# AirU_v2_0.net
KiCad netlist of a schematic drawn in EAGLE
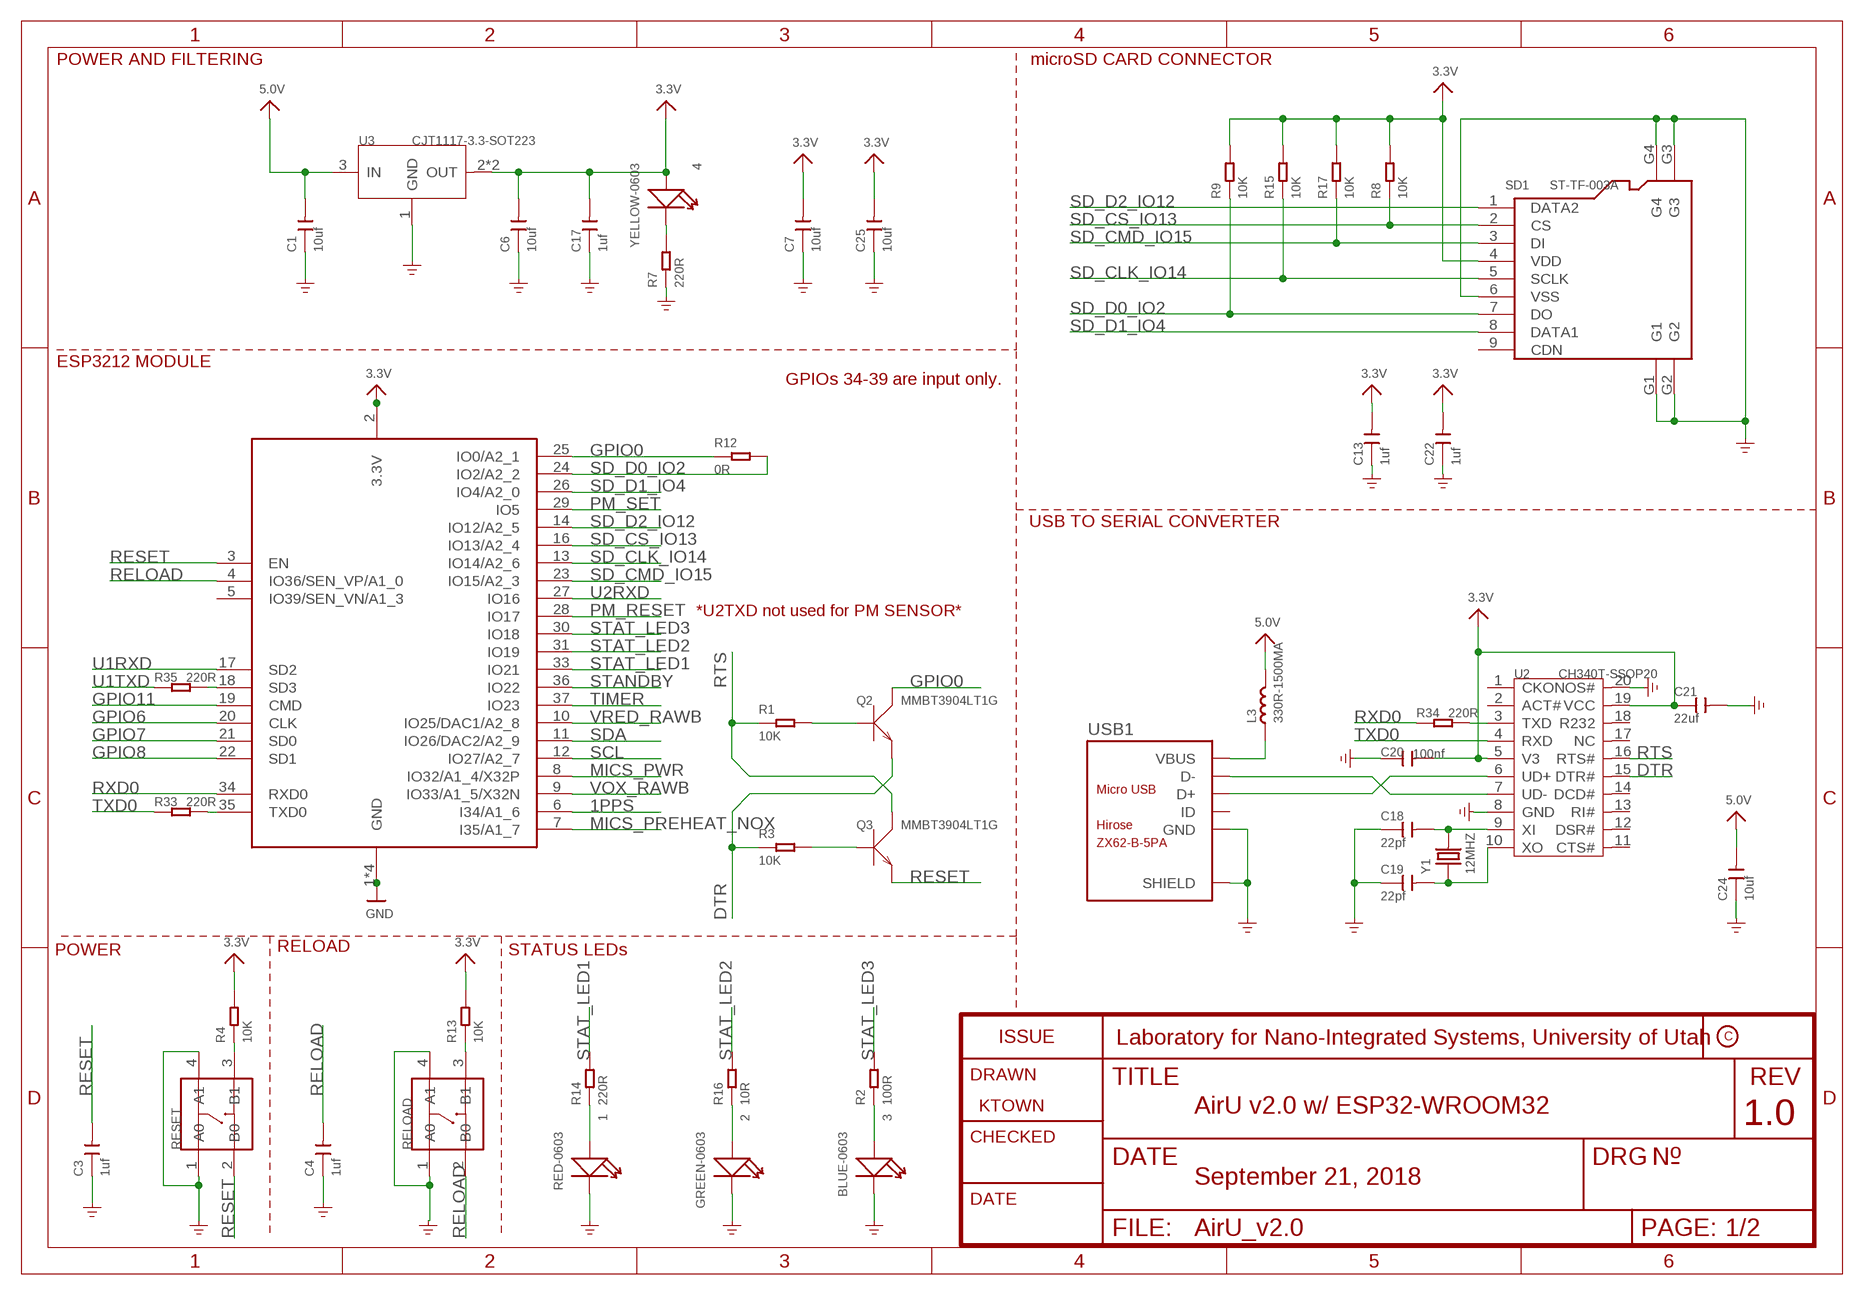
[diagram p0: schematic, sheet 1]
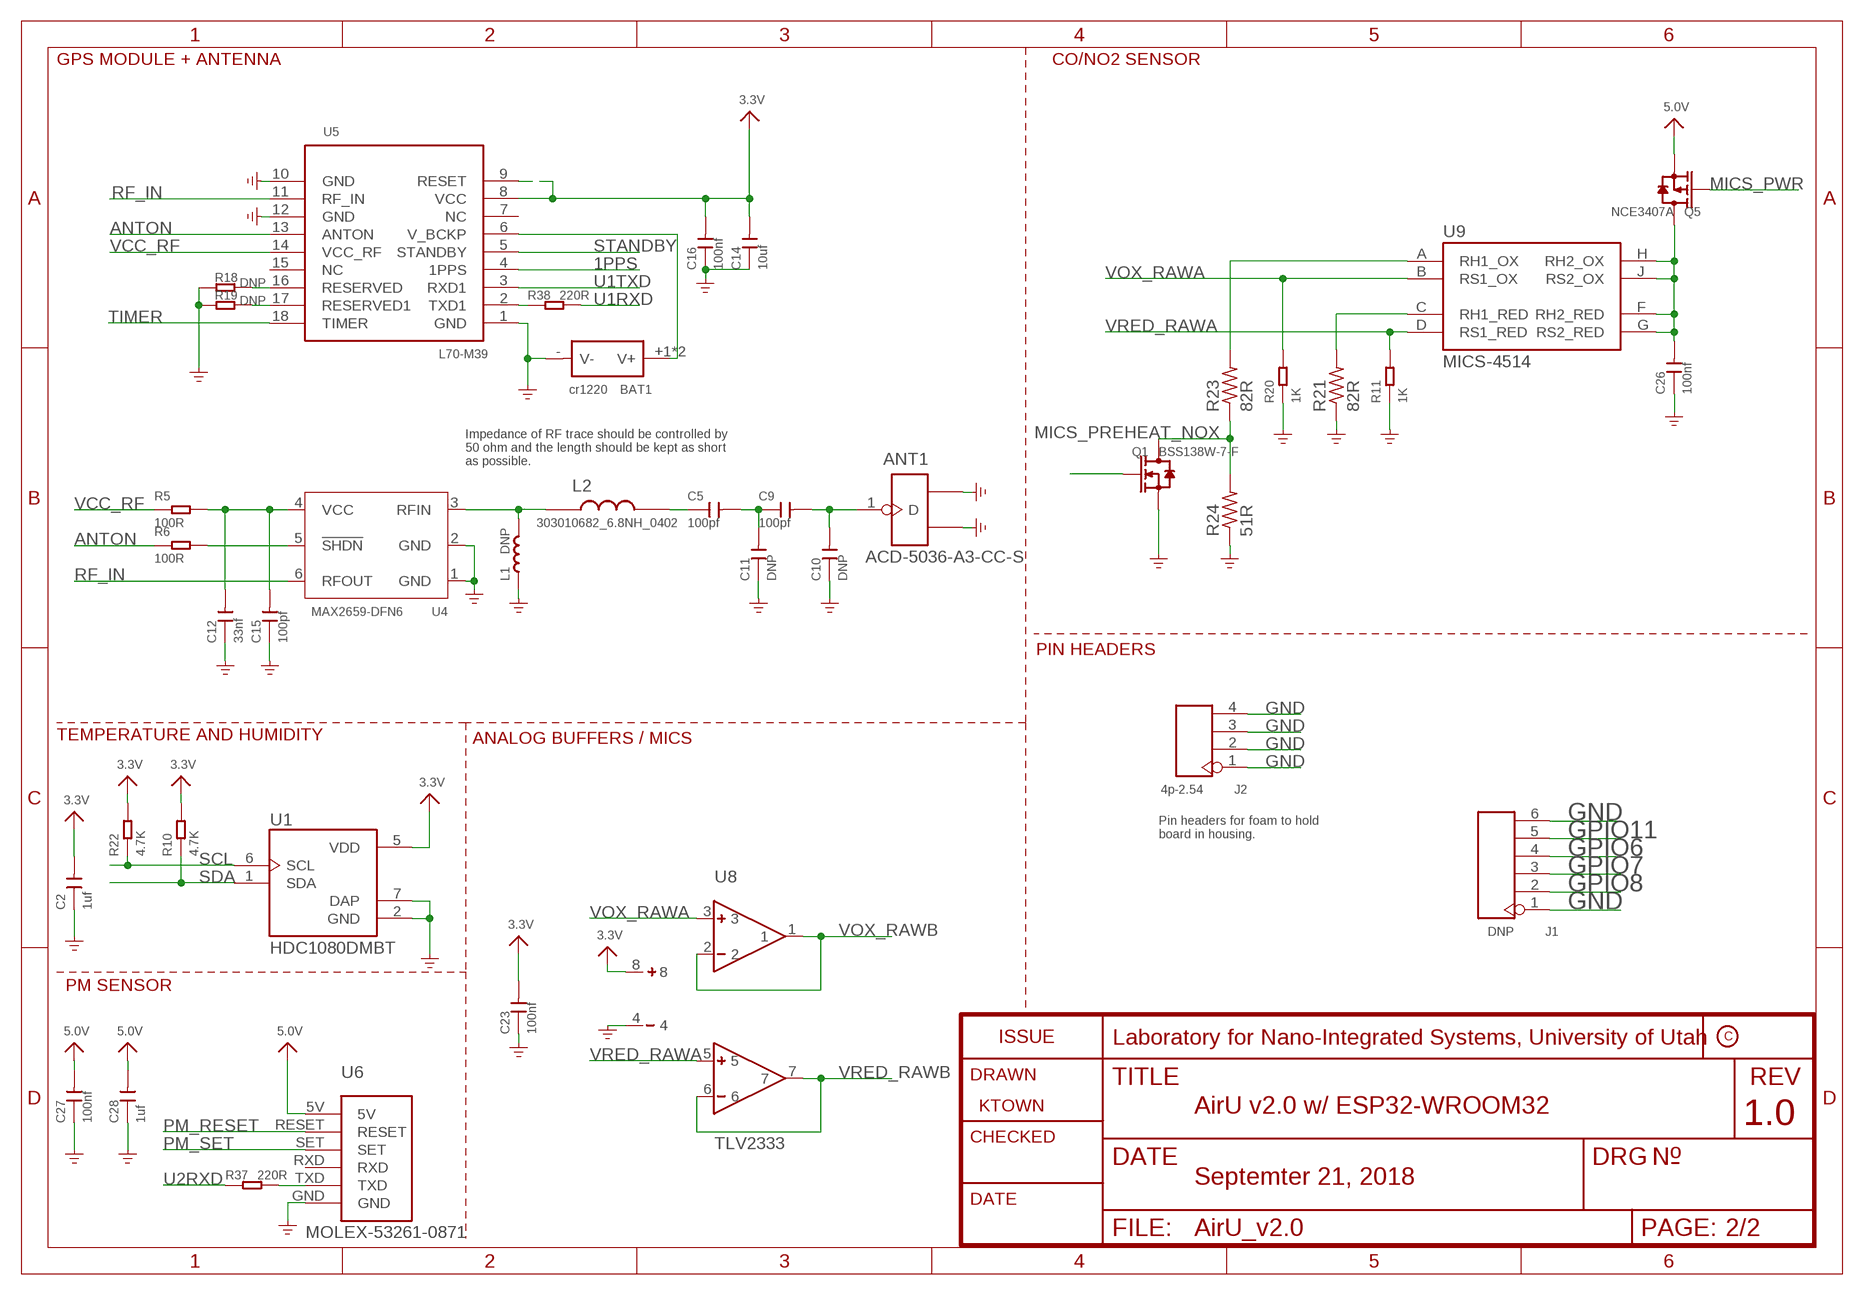
[diagram p1: schematic, sheet 2]

(export (version "E")
  (design (tool "Eeschema 10.0.6"))
  (components
    (comp (ref "1")
      (value "RED-0603")
      (footprint "eagle-import:LED-0603")
      (fields (field (name "MPN") "19-217-R6C-AL1M2VY-3T"))
      (libsource (lib "eagle-import") (part "LED-SMD-RED-DIFFUSED(0603)"))
    )
    (comp (ref "2")
      (value "GREEN-0603")
      (footprint "eagle-import:LED-0603")
      (fields (field (name "MPN") "19-217-G7C-AN1P2-3T"))
      (libsource (lib "eagle-import") (part "SMD-LED-CLEAR-GREEN(0603)"))
    )
    (comp (ref "3")
      (value "BLUE-0603")
      (footprint "eagle-import:LED-0603")
      (fields (field (name "MPN") "19-217-BHC-ZL1M2RY-3T"))
      (libsource (lib "eagle-import") (part "SMD-LED-CLEAR-BLUE(0603)"))
    )
    (comp (ref "4")
      (value "YELLOW-0603")
      (footprint "eagle-import:LED-0603")
      (fields (field (name "MPN") "19-217-Y5C-AM1N1VY-3T"))
      (libsource (lib "eagle-import") (part "SMD-LED-CLEAR-YELLOW(0603)"))
    )
    (comp (ref "C1")
      (value "10uf")
      (footprint "eagle-import:C0603")
      (fields (field (name "MPN") "CC0603KRX5R6BB106"))
      (libsource (lib "eagle-import") (part "CERAMIC-10UF-10V-10%-X5R(0603)"))
    )
    (comp (ref "C3")
      (value "1uf")
      (footprint "eagle-import:C0603")
      (fields (field (name "MPN") "CC0603KRX7R8BB105"))
      (libsource (lib "eagle-import") (part "CERAMIC-1UF-25V-10%-X7R(0603)"))
    )
    (comp (ref "C4")
      (value "1uf")
      (footprint "eagle-import:C0603")
      (fields (field (name "MPN") "CC0603KRX7R8BB105"))
      (libsource (lib "eagle-import") (part "CERAMIC-1UF-25V-10%-X7R(0603)"))
    )
    (comp (ref "C6")
      (value "10uf")
      (footprint "eagle-import:C0603")
      (fields (field (name "MPN") "CC0603KRX5R6BB106"))
      (libsource (lib "eagle-import") (part "CERAMIC-10UF-10V-10%-X5R(0603)"))
    )
    (comp (ref "C7")
      (value "10uf")
      (footprint "eagle-import:C0603")
      (fields (field (name "MPN") "CC0603KRX5R6BB106"))
      (libsource (lib "eagle-import") (part "CERAMIC-10UF-10V-10%-X5R(0603)"))
    )
    (comp (ref "C13")
      (value "1uf")
      (footprint "eagle-import:C0603")
      (fields (field (name "MPN") "CC0603KRX7R8BB105"))
      (libsource (lib "eagle-import") (part "CERAMIC-1UF-25V-10%-X7R(0603)"))
    )
    (comp (ref "C17")
      (value "1uf")
      (footprint "eagle-import:C0603")
      (fields (field (name "MPN") "CC0603KRX7R8BB105"))
      (libsource (lib "eagle-import") (part "CERAMIC-1UF-25V-10%-X7R(0603)"))
    )
    (comp (ref "C18")
      (value "22pf")
      (footprint "eagle-import:C0603")
      (fields (field (name "MPN") "CC0603JRNPO9BN220"))
      (libsource (lib "eagle-import") (part "CERAMIC-22PF-50V-5%-NPO(0603)"))
    )
    (comp (ref "C19")
      (value "22pf")
      (footprint "eagle-import:C0603")
      (fields (field (name "MPN") "CC0603JRNPO9BN220"))
      (libsource (lib "eagle-import") (part "CERAMIC-22PF-50V-5%-NPO(0603)"))
    )
    (comp (ref "C20")
      (value "100nf")
      (footprint "eagle-import:C0603")
      (fields (field (name "MPN") "CC0603KRX7R9BB104"))
      (libsource (lib "eagle-import") (part "CERAMIC-100NF-50V-10%-X7R(0603)"))
    )
    (comp (ref "C21")
      (value "22uf")
      (footprint "eagle-import:C0805")
      (fields (field (name "MPN") "CC0805MKX5R5BB226"))
      (libsource (lib "eagle-import") (part "CERAMIC-22UF-6.3V-20%-X5R(0805)"))
    )
    (comp (ref "C22")
      (value "1uf")
      (footprint "eagle-import:C0603")
      (fields (field (name "MPN") "CC0603KRX7R8BB105"))
      (libsource (lib "eagle-import") (part "CERAMIC-1UF-25V-10%-X7R(0603)"))
    )
    (comp (ref "C24")
      (value "10uf")
      (footprint "eagle-import:C0603")
      (fields (field (name "MPN") "CC0603KRX5R6BB106"))
      (libsource (lib "eagle-import") (part "CERAMIC-10UF-10V-10%-X5R(0603)"))
    )
    (comp (ref "C25")
      (value "10uf")
      (footprint "eagle-import:C0603")
      (fields (field (name "MPN") "CC0603KRX5R6BB106"))
      (libsource (lib "eagle-import") (part "CERAMIC-10UF-10V-10%-X5R(0603)"))
    )
    (comp (ref "L3")
      (value "330R-1500MA")
      (footprint "eagle-import:L0805")
      (fields (field (name "MPN") "BLM21PG331SN1D"))
      (libsource (lib "eagle-import") (part "SMD-FERRITE-BEAD-330R-1500MA(0805)'0805'"))
    )
    (comp (ref "Q2")
      (value "MMBT3904LT1G")
      (footprint "eagle-import:SOT-23")
      (libsource (lib "eagle-import") (part "SMD-TRANSISTORS-NPN-40V-200MA-MMBT3904LT1G(SOT-23)"))
    )
    (comp (ref "Q3")
      (value "MMBT3904LT1G")
      (footprint "eagle-import:SOT-23")
      (libsource (lib "eagle-import") (part "SMD-TRANSISTORS-NPN-40V-200MA-MMBT3904LT1G(SOT-23)"))
    )
    (comp (ref "R1")
      (value "10K")
      (footprint "eagle-import:R0603")
      (fields (field (name "MPN") "RC0603FR-0710KL"))
      (libsource (lib "eagle-import") (part "SMD-RES-10K-1%-1/10W(0603)"))
    )
    (comp (ref "R2")
      (value "100R")
      (footprint "eagle-import:R0603")
      (fields (field (name "MPN") "RC0603JR-07100RL"))
      (libsource (lib "eagle-import") (part "SMD-RES-100R-5%-1/10W(0603)"))
    )
    (comp (ref "R3")
      (value "10K")
      (footprint "eagle-import:R0603")
      (fields (field (name "MPN") "RC0603FR-0710KL"))
      (libsource (lib "eagle-import") (part "SMD-RES-10K-1%-1/10W(0603)"))
    )
    (comp (ref "R4")
      (value "10K")
      (footprint "eagle-import:R0603")
      (fields (field (name "MPN") "RC0603FR-0710KL"))
      (libsource (lib "eagle-import") (part "SMD-RES-10K-1%-1/10W(0603)"))
    )
    (comp (ref "R7")
      (value "220R")
      (footprint "eagle-import:R0603")
      (fields (field (name "MPN") "RC0603JR-07220RL"))
      (libsource (lib "eagle-import") (part "SMD-RES-220R-5%-1/10W(0603)"))
    )
    (comp (ref "R8")
      (value "10K")
      (footprint "eagle-import:R0603")
      (fields (field (name "MPN") "RC0603FR-0710KL"))
      (libsource (lib "eagle-import") (part "SMD-RES-10K-1%-1/10W(0603)"))
    )
    (comp (ref "R9")
      (value "10K")
      (footprint "eagle-import:R0603")
      (fields (field (name "MPN") "RC0603FR-0710KL"))
      (libsource (lib "eagle-import") (part "SMD-RES-10K-1%-1/10W(0603)"))
    )
    (comp (ref "R12")
      (value "0R")
      (footprint "eagle-import:R0603")
      (fields (field (name "MPN") "RC0603JR-070RL"))
      (libsource (lib "eagle-import") (part "SMD-RES-0R-5%-1/10W(0603)"))
    )
    (comp (ref "R13")
      (value "10K")
      (footprint "eagle-import:R0603")
      (fields (field (name "MPN") "RC0603FR-0710KL"))
      (libsource (lib "eagle-import") (part "SMD-RES-10K-1%-1/10W(0603)"))
    )
    (comp (ref "R14")
      (value "220R")
      (footprint "eagle-import:R0603")
      (fields (field (name "MPN") "RC0603JR-07220RL"))
      (libsource (lib "eagle-import") (part "SMD-RES-220R-5%-1/10W(0603)"))
    )
    (comp (ref "R15")
      (value "10K")
      (footprint "eagle-import:R0603")
      (fields (field (name "MPN") "RC0603FR-0710KL"))
      (libsource (lib "eagle-import") (part "SMD-RES-10K-1%-1/10W(0603)"))
    )
    (comp (ref "R16")
      (value "10R")
      (footprint "eagle-import:R0603")
      (fields (field (name "MPN") "RC0603JR-0710RL"))
      (libsource (lib "eagle-import") (part "SMD-RES-10R-5%-1/10W(0603)"))
    )
    (comp (ref "R17")
      (value "10K")
      (footprint "eagle-import:R0603")
      (fields (field (name "MPN") "RC0603FR-0710KL"))
      (libsource (lib "eagle-import") (part "SMD-RES-10K-1%-1/10W(0603)"))
    )
    (comp (ref "R33")
      (value "220R")
      (footprint "eagle-import:R0603")
      (fields (field (name "MPN") "RC0603JR-07220RL"))
      (libsource (lib "eagle-import") (part "SMD-RES-220R-5%-1/10W(0603)"))
    )
    (comp (ref "R34")
      (value "220R")
      (footprint "eagle-import:R0603")
      (fields (field (name "MPN") "RC0603JR-07220RL"))
      (libsource (lib "eagle-import") (part "SMD-RES-220R-5%-1/10W(0603)"))
    )
    (comp (ref "R35")
      (value "220R")
      (footprint "eagle-import:R0603")
      (fields (field (name "MPN") "RC0603JR-07220RL"))
      (libsource (lib "eagle-import") (part "SMD-RES-220R-5%-1/10W(0603)"))
    )
    (comp (ref "RELOAD")
      (value "DIP-SWITCH-TACTILE-SPST-NO/TS-1109(4P-D6.0MM)'TS-1109'")
      (footprint "eagle-import:SW4-6.0X6.0X5.0MM")
      (libsource (lib "eagle-import") (part "DIP-SWITCH-TACTILE-SPST-NO/TS-1109(4P-D6.0MM)'TS-1109'"))
    )
    (comp (ref "RESET")
      (value "DIP-SWITCH-TACTILE-SPST-NO/TS-1109(4P-D6.0MM)'TS-1109'")
      (footprint "eagle-import:SW4-6.0X6.0X5.0MM")
      (libsource (lib "eagle-import") (part "DIP-SWITCH-TACTILE-SPST-NO/TS-1109(4P-D6.0MM)'TS-1109'"))
    )
    (comp (ref "SD1")
      (value "ST-TF-003A")
      (footprint "eagle-import:MICRO-SD9+4P-SMD-16.1X14.5X1.85MM")
      (libsource (lib "eagle-import") (part "MICRO-SD-CARD-SOCKET-9P(ST-TF-003A)"))
    )
    (comp (ref "U2")
      (value "CH340T-SSOP20")
      (footprint "eagle-import:SSOP20-0.65-7.6X5.2MM")
      (fields (field (name "MPN") "CH340T"))
      (libsource (lib "eagle-import") (part "INTERFACE-CH340T(SSOP20)"))
    )
    (comp (ref "U3")
      (value "CJT1117-3.3-SOT223")
      (footprint "eagle-import:SOT-223")
      (fields (field (name "MPN") "CJT1117-3.3"))
      (libsource (lib "eagle-import") (part "PMIC-CJT1117-3.3(SOT223)"))
    )
    (comp (ref "U7")
      (value "ESP32_WROOM32_SKINNY")
      (footprint "eagle-import:WROOM32_SKINNY")
      (libsource (lib "eagle-import") (part "ESP32_WROOM32_SKINNY"))
    )
    (comp (ref "USB1")
      (value "ZX62-B-5PA")
      (footprint "eagle-import:MICRO-USB5+6P-SMD-0.65-AB")
      (libsource (lib "eagle-import") (part "MICRO-USB-SMD(ZX62-B-5PA)"))
    )
    (comp (ref "Y1")
      (value "12MHZ")
      (footprint "eagle-import:X2-SMD-5.0X3.2X1.3MM")
      (fields (field (name "MPN") "5032/2P"))
      (libsource (lib "eagle-import") (part "SMD-CRYSTAL-12MHZ-20PF-20PPM-40R(2P-5.0X3.2MM)"))
    )
    (comp (ref "ANT1")
      (value "ACD-5036-A3-CC-S")
      (footprint "eagle-import:ANT3-SMD-5.2X3.7X0.7MM")
      (libsource (lib "eagle-import") (part "ANTENNA-ACD5036"))
    )
    (comp (ref "BAT1")
      (value "cr1220")
      (footprint "eagle-import:BAT2P-13.5-CR1220")
      (libsource (lib "eagle-import") (part "DIP-BATTERY-CELL-HOLDER(1220)"))
    )
    (comp (ref "C2")
      (value "1uf")
      (footprint "eagle-import:C0603")
      (fields (field (name "MPN") "CC0603KRX7R8BB105"))
      (libsource (lib "eagle-import") (part "CERAMIC-1UF-25V-10%-X7R(0603)"))
    )
    (comp (ref "C5")
      (value "100pf")
      (footprint "eagle-import:C0603")
      (fields (field (name "MPN") "CC0603JRNPO9BN101"))
      (libsource (lib "eagle-import") (part "CERAMIC-100PF-50V-5%-NPO(0603)"))
    )
    (comp (ref "C9")
      (value "100pf")
      (footprint "eagle-import:C0603")
      (fields (field (name "MPN") "CC0603JRNPO9BN101"))
      (libsource (lib "eagle-import") (part "CERAMIC-100PF-50V-5%-NPO(0603)"))
    )
    (comp (ref "C10")
      (value "DNP")
      (footprint "eagle-import:C0603")
      (fields (field (name "MPN") "CC0603JRNPO9BN101"))
      (libsource (lib "eagle-import") (part "CERAMIC-100PF-50V-5%-NPO(0603)"))
    )
    (comp (ref "C11")
      (value "DNP")
      (footprint "eagle-import:C0603")
      (fields (field (name "MPN") "CC0603JRNPO9BN101"))
      (libsource (lib "eagle-import") (part "CERAMIC-100PF-50V-5%-NPO(0603)"))
    )
    (comp (ref "C12")
      (value "33nf")
      (footprint "eagle-import:C0603")
      (fields (field (name "MPN") "CC0603KRX7R9BB333"))
      (libsource (lib "eagle-import") (part "CERAMIC-33NF-50V-10%-X7R(0603)"))
    )
    (comp (ref "C14")
      (value "10uf")
      (footprint "eagle-import:C0603")
      (fields (field (name "MPN") "CC0603KRX5R6BB106"))
      (libsource (lib "eagle-import") (part "CERAMIC-10UF-10V-10%-X5R(0603)"))
    )
    (comp (ref "C15")
      (value "100pf")
      (footprint "eagle-import:C0603")
      (fields (field (name "MPN") "CC0603JRNPO9BN101"))
      (libsource (lib "eagle-import") (part "CERAMIC-100PF-50V-5%-NPO(0603)"))
    )
    (comp (ref "C16")
      (value "100nf")
      (footprint "eagle-import:C0603")
      (fields (field (name "MPN") "CC0603KRX7R9BB104"))
      (libsource (lib "eagle-import") (part "CERAMIC-100NF-50V-10%-X7R(0603)"))
    )
    (comp (ref "C23")
      (value "100nf")
      (footprint "eagle-import:C0603")
      (fields (field (name "MPN") "CC0603KRX7R9BB104"))
      (libsource (lib "eagle-import") (part "CERAMIC-100NF-50V-10%-X7R(0603)"))
    )
    (comp (ref "C26")
      (value "100nf")
      (footprint "eagle-import:C0603")
      (fields (field (name "MPN") "CC0603KRX7R9BB104"))
      (libsource (lib "eagle-import") (part "CERAMIC-100NF-50V-10%-X7R(0603)"))
    )
    (comp (ref "C27")
      (value "100nf")
      (footprint "eagle-import:C0603")
      (fields (field (name "MPN") "CC0603KRX7R9BB104"))
      (libsource (lib "eagle-import") (part "CERAMIC-100NF-50V-10%-X7R(0603)"))
    )
    (comp (ref "C28")
      (value "1uf")
      (footprint "eagle-import:C0603")
      (fields (field (name "MPN") "CC0603KRX7R8BB105"))
      (libsource (lib "eagle-import") (part "CERAMIC-1UF-25V-10%-X7R(0603)"))
    )
    (comp (ref "J1")
      (value "DNP")
      (footprint "eagle-import:H6-2.54")
      (fields (field (name "MPN") "P125-1106A1BS116A1"))
      (libsource (lib "eagle-import") (part "DIP-BLACK-MALE-HEADER(6P-2.54)"))
    )
    (comp (ref "J2")
      (value "4p-2.54")
      (footprint "eagle-import:H4-2.54")
      (fields (field (name "MPN") "P125-1104A0BS116A1"))
      (libsource (lib "eagle-import") (part "DIP-BLACK-MALE-HEADER-VERT(4P-2.54)"))
    )
    (comp (ref "L1")
      (value "DNP")
      (footprint "eagle-import:L0201")
      (libsource (lib "eagle-import") (part "INDUCTOR/FERRITE-BEAD-0201"))
    )
    (comp (ref "L2")
      (value "303010682_6.8NH_0402")
      (footprint "eagle-import:L0402")
      (libsource (lib "eagle-import") (part "303010682_6.8NH_0402"))
    )
    (comp (ref "Q1")
      (value "BSS138W-7-F")
      (footprint "eagle-import:SOT-23")
      (libsource (lib "eagle-import") (part "SMD-MOSFET-N-CH-50V-200MA-BSS138W-7-F(SOT-23)"))
    )
    (comp (ref "Q5")
      (value "NCE3407A")
      (footprint "eagle-import:SOT-23")
      (libsource (lib "eagle-import") (part "SMD-MOSFET-P-CH-VDC=30V-ID=4.3A-NCE3407A(SOT-23)"))
    )
    (comp (ref "R5")
      (value "100R")
      (footprint "eagle-import:R0603")
      (fields (field (name "MPN") "RC0603JR-07100RL"))
      (libsource (lib "eagle-import") (part "SMD-RES-100R-5%-1/10W(0603)"))
    )
    (comp (ref "R6")
      (value "100R")
      (footprint "eagle-import:R0603")
      (fields (field (name "MPN") "RC0603JR-07100RL"))
      (libsource (lib "eagle-import") (part "SMD-RES-100R-5%-1/10W(0603)"))
    )
    (comp (ref "R10")
      (value "4.7K")
      (footprint "eagle-import:R0603")
      (fields (field (name "MPN") "RC0603JR-074K7L"))
      (libsource (lib "eagle-import") (part "SMD-RES-4.7K-5%-1/10W(0603)"))
    )
    (comp (ref "R11")
      (value "1K")
      (footprint "eagle-import:R0603")
      (fields (field (name "MPN") "RC0603FR-071KL"))
      (libsource (lib "eagle-import") (part "SMD-RES-1K-1%-1/10W(0603)"))
    )
    (comp (ref "R18")
      (value "DNP")
      (footprint "eagle-import:R0603")
      (fields (field (name "MPN") "RC0603FR-0710KL"))
      (libsource (lib "eagle-import") (part "SMD-RES-10K-1%-1/10W(0603)"))
    )
    (comp (ref "R19")
      (value "DNP")
      (footprint "eagle-import:R0603")
      (fields (field (name "MPN") "RC0603FR-0710KL"))
      (libsource (lib "eagle-import") (part "SMD-RES-10K-1%-1/10W(0603)"))
    )
    (comp (ref "R20")
      (value "1K")
      (footprint "eagle-import:R0603")
      (fields (field (name "MPN") "RC0603FR-071KL"))
      (libsource (lib "eagle-import") (part "SMD-RES-1K-1%-1/10W(0603)"))
    )
    (comp (ref "R21")
      (value "82R")
      (footprint "eagle-import:R0603")
      (libsource (lib "eagle-import") (part "R-US_R0603"))
    )
    (comp (ref "R22")
      (value "4.7K")
      (footprint "eagle-import:R0603")
      (fields (field (name "MPN") "RC0603JR-074K7L"))
      (libsource (lib "eagle-import") (part "SMD-RES-4.7K-5%-1/10W(0603)"))
    )
    (comp (ref "R23")
      (value "82R")
      (footprint "eagle-import:R0603")
      (libsource (lib "eagle-import") (part "R-US_R0603"))
    )
    (comp (ref "R24")
      (value "51R")
      (footprint "eagle-import:R0603")
      (libsource (lib "eagle-import") (part "R-US_R0603"))
    )
    (comp (ref "R37")
      (value "220R")
      (footprint "eagle-import:R0603")
      (fields (field (name "MPN") "RC0603JR-07220RL"))
      (libsource (lib "eagle-import") (part "SMD-RES-220R-5%-1/10W(0603)"))
    )
    (comp (ref "R38")
      (value "220R")
      (footprint "eagle-import:R0603")
      (fields (field (name "MPN") "RC0603JR-07220RL"))
      (libsource (lib "eagle-import") (part "SMD-RES-220R-5%-1/10W(0603)"))
    )
    (comp (ref "U1")
      (value "HDC1080DMBT")
      (footprint "eagle-import:SON100P300X300X80-7N")
      (fields (field (name "DIGI-KEY_PART_NUMBER") "296-43864-1-ND") (field (name "MF") "Texas Instruments"))
      (libsource (lib "eagle-import") (part "HDC1080DMBT"))
    )
    (comp (ref "U4")
      (value "MAX2659-DFN6")
      (footprint "eagle-import:DFN6-0.5-1.5X1.2X0.72MM")
      (fields (field (name "MPN") "MAX2659"))
      (libsource (lib "eagle-import") (part "AMPLIFIER-MAX2659"))
    )
    (comp (ref "U5")
      (value "L70-M39")
      (footprint "eagle-import:LGA18-1.1-9.7X10.1X2.5MM")
      (fields (field (name "MPN") "L70"))
      (libsource (lib "eagle-import") (part "MOUDLE-GPS-L70-HARDWARE"))
    )
    (comp (ref "U6")
      (value "MOLEX-53261-0871")
      (footprint "eagle-import:MOLEX-53261-0871")
      (libsource (lib "eagle-import") (part "MOLEX-53261-0871"))
    )
    (comp (ref "U8")
      (value "TLV2333")
      (footprint "eagle-import:TLV2333")
      (libsource (lib "eagle-import") (part "TLV2333"))
    )
    (comp (ref "U9")
      (value "MICS-4514")
      (footprint "eagle-import:MICS_10-SMD")
      (fields (field (name "MF") "Amphenol"))
      (libsource (lib "eagle-import") (part "MICS-4514"))
    )
  )
  (nets
    (net (code "1") (name "1PPS") (class "Default")
      (node (ref "U5") (pin "4") (pinfunction "1PPS_4") (pintype "bidirectional"))
      (node (ref "U7") (pin "6") (pinfunction "I34/A1_6_6") (pintype "bidirectional"))
    )
    (net (code "2") (name "3.3V") (class "Default")
      (node (ref "4") (pin "+") (pinfunction "+_+") (pintype "passive"))
      (node (ref "C13") (pin "2") (pinfunction "2_2") (pintype "passive"))
      (node (ref "C14") (pin "2") (pinfunction "2_2") (pintype "passive"))
      (node (ref "C16") (pin "2") (pinfunction "2_2") (pintype "passive"))
      (node (ref "C17") (pin "2") (pinfunction "2_2") (pintype "passive"))
      (node (ref "C2") (pin "2") (pinfunction "2_2") (pintype "passive"))
      (node (ref "C20") (pin "2") (pinfunction "2_2") (pintype "passive"))
      (node (ref "C21") (pin "1") (pinfunction "1_1") (pintype "passive"))
      (node (ref "C22") (pin "2") (pinfunction "2_2") (pintype "passive"))
      (node (ref "C23") (pin "2") (pinfunction "2_2") (pintype "passive"))
      (node (ref "C25") (pin "2") (pinfunction "2_2") (pintype "passive"))
      (node (ref "C6") (pin "2") (pinfunction "2_2") (pintype "passive"))
      (node (ref "C7") (pin "2") (pinfunction "2_2") (pintype "passive"))
      (node (ref "R10") (pin "2") (pinfunction "2_2") (pintype "passive"))
      (node (ref "R13") (pin "2") (pinfunction "2_2") (pintype "passive"))
      (node (ref "R15") (pin "2") (pinfunction "2_2") (pintype "passive"))
      (node (ref "R17") (pin "2") (pinfunction "2_2") (pintype "passive"))
      (node (ref "R22") (pin "2") (pinfunction "2_2") (pintype "passive"))
      (node (ref "R4") (pin "2") (pinfunction "2_2") (pintype "passive"))
      (node (ref "R8") (pin "2") (pinfunction "2_2") (pintype "passive"))
      (node (ref "R9") (pin "2") (pinfunction "2_2") (pintype "passive"))
      (node (ref "SD1") (pin "4") (pinfunction "VDD_4") (pintype "bidirectional"))
      (node (ref "U1") (pin "5") (pinfunction "VDD_5") (pintype "power_in"))
      (node (ref "U2") (pin "19") (pinfunction "VCC_19") (pintype "power_in"))
      (node (ref "U2") (pin "5") (pinfunction "V3_5") (pintype "power_in"))
      (node (ref "U3") (pin "2") (pinfunction "OUT_2") (pintype "bidirectional"))
      (node (ref "U3") (pin "TER") (pinfunction "OUT_TER") (pintype "bidirectional"))
      (node (ref "U5") (pin "8") (pinfunction "VCC_8") (pintype "power_in"))
      (node (ref "U5") (pin "9") (pinfunction "RESET_9") (pintype "bidirectional"))
      (node (ref "U7") (pin "2") (pinfunction "3.3V_2") (pintype "passive"))
      (node (ref "U8") (pin "8") (pinfunction "8_8") (pintype "bidirectional"))
    )
    (net (code "3") (name "5.0V") (class "Default")
      (node (ref "C1") (pin "2") (pinfunction "2_2") (pintype "passive"))
      (node (ref "C24") (pin "2") (pinfunction "2_2") (pintype "passive"))
      (node (ref "C27") (pin "2") (pinfunction "2_2") (pintype "passive"))
      (node (ref "C28") (pin "2") (pinfunction "2_2") (pintype "passive"))
      (node (ref "L3") (pin "2") (pinfunction "2_2") (pintype "passive"))
      (node (ref "Q5") (pin "2") (pinfunction "S_2") (pintype "passive"))
      (node (ref "U3") (pin "3") (pinfunction "IN_3") (pintype "bidirectional"))
      (node (ref "U6") (pin "5V") (pinfunction "5V_5V") (pintype "bidirectional"))
    )
    (net (code "4") (name "ANTON") (class "Default")
      (node (ref "R6") (pin "1") (pinfunction "1_1") (pintype "passive"))
      (node (ref "U5") (pin "13") (pinfunction "ANTON_13") (pintype "bidirectional"))
    )
    (net (code "5") (name "DTR") (class "Default")
      (node (ref "Q2") (pin "2") (pinfunction "E_2") (pintype "passive"))
      (node (ref "R3") (pin "1") (pinfunction "1_1") (pintype "passive"))
      (node (ref "U2") (pin "15") (pinfunction "DTR#_15") (pintype "output"))
    )
    (net (code "6") (name "GND") (class "Default")
      (node (ref "1") (pin "-") (pinfunction "-_-") (pintype "passive"))
      (node (ref "2") (pin "-") (pinfunction "-_-") (pintype "passive"))
      (node (ref "3") (pin "-") (pinfunction "-_-") (pintype "passive"))
      (node (ref "ANT1") (pin "2") (pinfunction "GND1_2") (pintype "bidirectional"))
      (node (ref "ANT1") (pin "3") (pinfunction "GND2_3") (pintype "bidirectional"))
      (node (ref "BAT1") (pin "-") (pinfunction "V-_-") (pintype "bidirectional"))
      (node (ref "C1") (pin "1") (pinfunction "1_1") (pintype "passive"))
      (node (ref "C10") (pin "1") (pinfunction "1_1") (pintype "passive"))
      (node (ref "C11") (pin "1") (pinfunction "1_1") (pintype "passive"))
      (node (ref "C12") (pin "1") (pinfunction "1_1") (pintype "passive"))
      (node (ref "C13") (pin "1") (pinfunction "1_1") (pintype "passive"))
      (node (ref "C14") (pin "1") (pinfunction "1_1") (pintype "passive"))
      (node (ref "C15") (pin "1") (pinfunction "1_1") (pintype "passive"))
      (node (ref "C16") (pin "1") (pinfunction "1_1") (pintype "passive"))
      (node (ref "C17") (pin "1") (pinfunction "1_1") (pintype "passive"))
      (node (ref "C18") (pin "1") (pinfunction "1_1") (pintype "passive"))
      (node (ref "C19") (pin "1") (pinfunction "1_1") (pintype "passive"))
      (node (ref "C2") (pin "1") (pinfunction "1_1") (pintype "passive"))
      (node (ref "C20") (pin "1") (pinfunction "1_1") (pintype "passive"))
      (node (ref "C21") (pin "2") (pinfunction "2_2") (pintype "passive"))
      (node (ref "C22") (pin "1") (pinfunction "1_1") (pintype "passive"))
      (node (ref "C23") (pin "1") (pinfunction "1_1") (pintype "passive"))
      (node (ref "C24") (pin "1") (pinfunction "1_1") (pintype "passive"))
      (node (ref "C25") (pin "1") (pinfunction "1_1") (pintype "passive"))
      (node (ref "C26") (pin "1") (pinfunction "1_1") (pintype "passive"))
      (node (ref "C27") (pin "1") (pinfunction "1_1") (pintype "passive"))
      (node (ref "C28") (pin "1") (pinfunction "1_1") (pintype "passive"))
      (node (ref "C3") (pin "1") (pinfunction "1_1") (pintype "passive"))
      (node (ref "C4") (pin "1") (pinfunction "1_1") (pintype "passive"))
      (node (ref "C6") (pin "1") (pinfunction "1_1") (pintype "passive"))
      (node (ref "C7") (pin "1") (pinfunction "1_1") (pintype "passive"))
      (node (ref "J1") (pin "1") (pinfunction "1_1") (pintype "bidirectional"))
      (node (ref "J1") (pin "6") (pinfunction "6_6") (pintype "bidirectional"))
      (node (ref "J2") (pin "1") (pinfunction "P$1_1") (pintype "bidirectional"))
      (node (ref "J2") (pin "2") (pinfunction "P$2_2") (pintype "bidirectional"))
      (node (ref "J2") (pin "3") (pinfunction "P$3_3") (pintype "bidirectional"))
      (node (ref "J2") (pin "4") (pinfunction "P$4_4") (pintype "bidirectional"))
      (node (ref "L1") (pin "1") (pinfunction "1_1") (pintype "passive"))
      (node (ref "Q1") (pin "2") (pinfunction "S_2") (pintype "passive"))
      (node (ref "R11") (pin "1") (pinfunction "1_1") (pintype "passive"))
      (node (ref "R18") (pin "1") (pinfunction "1_1") (pintype "passive"))
      (node (ref "R19") (pin "1") (pinfunction "1_1") (pintype "passive"))
      (node (ref "R20") (pin "1") (pinfunction "1_1") (pintype "passive"))
      (node (ref "R21") (pin "1") (pinfunction "1_1") (pintype "passive"))
      (node (ref "R24") (pin "1") (pinfunction "1_1") (pintype "passive"))
      (node (ref "R7") (pin "1") (pinfunction "1_1") (pintype "passive"))
      (node (ref "RELOAD") (pin "1") (pinfunction "A0_1") (pintype "bidirectional"))
      (node (ref "RELOAD") (pin "4") (pinfunction "A1_4") (pintype "bidirectional"))
      (node (ref "RESET") (pin "1") (pinfunction "A0_1") (pintype "bidirectional"))
      (node (ref "RESET") (pin "4") (pinfunction "A1_4") (pintype "bidirectional"))
      (node (ref "SD1") (pin "6") (pinfunction "VSS_6") (pintype "bidirectional"))
      (node (ref "SD1") (pin "G1") (pinfunction "G1_G1") (pintype "bidirectional"))
      (node (ref "SD1") (pin "G2") (pinfunction "G2_G2") (pintype "bidirectional"))
      (node (ref "SD1") (pin "G3") (pinfunction "G3_G3") (pintype "bidirectional"))
      (node (ref "SD1") (pin "G4") (pinfunction "G4_G4") (pintype "bidirectional"))
      (node (ref "U1") (pin "2") (pinfunction "GND_2") (pintype "power_in"))
      (node (ref "U1") (pin "7") (pinfunction "DAP_7") (pintype "power_in"))
      (node (ref "U2") (pin "20") (pinfunction "NOS#_20") (pintype "power_in"))
      (node (ref "U2") (pin "8") (pinfunction "GND_8") (pintype "power_in"))
      (node (ref "U3") (pin "1") (pinfunction "GND_1") (pintype "bidirectional"))
      (node (ref "U4") (pin "1") (pinfunction "GND_1") (pintype "power_in"))
      (node (ref "U4") (pin "2") (pinfunction "GND_2") (pintype "power_in"))
      (node (ref "U5") (pin "1") (pinfunction "GND_1") (pintype "power_in"))
      (node (ref "U5") (pin "10") (pinfunction "GND_10") (pintype "power_in"))
      (node (ref "U5") (pin "12") (pinfunction "GND_12") (pintype "bidirectional"))
      (node (ref "U6") (pin "GND") (pinfunction "GND_GND") (pintype "bidirectional"))
      (node (ref "U7") (pin "1") (pinfunction "GND_1") (pintype "passive"))
      (node (ref "U7") (pin "15") (pinfunction "GND_15") (pintype "passive"))
      (node (ref "U7") (pin "38") (pinfunction "GND_38") (pintype "passive"))
      (node (ref "U7") (pin "P$1") (pinfunction "GND_P$1") (pintype "passive"))
      (node (ref "U8") (pin "4") (pinfunction "4_4") (pintype "bidirectional"))
      (node (ref "USB1") (pin "5") (pinfunction "GND_5") (pintype "power_in"))
      (node (ref "USB1") (pin "P1") (pinfunction "SHIELD_P1") (pintype "power_in"))
      (node (ref "USB1") (pin "P2") (pinfunction "SHIELD_P2") (pintype "power_in"))
      (node (ref "USB1") (pin "P3_1") (pinfunction "SHIELD_P3_1") (pintype "power_in"))
      (node (ref "USB1") (pin "P3_2") (pinfunction "SHIELD_P3_2") (pintype "power_in"))
      (node (ref "USB1") (pin "P3_3") (pinfunction "SHIELD_P3_3") (pintype "power_in"))
      (node (ref "USB1") (pin "P4_1") (pinfunction "SHIELD_P4_1") (pintype "power_in"))
      (node (ref "USB1") (pin "P4_2") (pinfunction "SHIELD_P4_2") (pintype "power_in"))
      (node (ref "USB1") (pin "P4_3") (pinfunction "SHIELD_P4_3") (pintype "power_in"))
      (node (ref "USB1") (pin "P5") (pinfunction "SHIELD_P5") (pintype "power_in"))
      (node (ref "USB1") (pin "P6") (pinfunction "SHIELD_P6") (pintype "power_in"))
    )
    (net (code "7") (name "GPIO0") (class "Default")
      (node (ref "Q2") (pin "3") (pinfunction "C_3") (pintype "passive"))
      (node (ref "R12") (pin "1") (pinfunction "1_1") (pintype "passive"))
      (node (ref "U7") (pin "25") (pinfunction "IO0/A2_1_25") (pintype "bidirectional"))
    )
    (net (code "8") (name "GPIO6") (class "Default")
      (node (ref "J1") (pin "4") (pinfunction "4_4") (pintype "bidirectional"))
      (node (ref "U7") (pin "20") (pinfunction "CLK_20") (pintype "bidirectional"))
    )
    (net (code "9") (name "GPIO7") (class "Default")
      (node (ref "J1") (pin "3") (pinfunction "3_3") (pintype "bidirectional"))
      (node (ref "U7") (pin "21") (pinfunction "SD0_21") (pintype "bidirectional"))
    )
    (net (code "10") (name "GPIO8") (class "Default")
      (node (ref "J1") (pin "2") (pinfunction "2_2") (pintype "bidirectional"))
      (node (ref "U7") (pin "22") (pinfunction "SD1_22") (pintype "bidirectional"))
    )
    (net (code "11") (name "GPIO11") (class "Default")
      (node (ref "J1") (pin "5") (pinfunction "5_5") (pintype "bidirectional"))
      (node (ref "U7") (pin "19") (pinfunction "CMD_19") (pintype "bidirectional"))
    )
    (net (code "12") (name "MICS_PREHEAT_NOX") (class "Default")
      (node (ref "Q1") (pin "1") (pinfunction "G_1") (pintype "passive"))
      (node (ref "U7") (pin "7") (pinfunction "I35/A1_7_7") (pintype "bidirectional"))
    )
    (net (code "13") (name "MICS_PWR") (class "Default")
      (node (ref "Q5") (pin "1") (pinfunction "G_1") (pintype "passive"))
      (node (ref "U7") (pin "8") (pinfunction "IO32/A1_4/X32P_8") (pintype "bidirectional"))
    )
    (net (code "14") (name "Net-(1-Pad+)") (class "Default")
      (node (ref "1") (pin "+") (pinfunction "+_+") (pintype "passive"))
      (node (ref "R14") (pin "1") (pinfunction "1_1") (pintype "passive"))
    )
    (net (code "15") (name "Net-(2-Pad+)") (class "Default")
      (node (ref "2") (pin "+") (pinfunction "+_+") (pintype "passive"))
      (node (ref "R16") (pin "1") (pinfunction "1_1") (pintype "passive"))
    )
    (net (code "16") (name "Net-(3-Pad+)") (class "Default")
      (node (ref "3") (pin "+") (pinfunction "+_+") (pintype "passive"))
      (node (ref "R2") (pin "1") (pinfunction "1_1") (pintype "passive"))
    )
    (net (code "17") (name "Net-(4-Pad-)") (class "Default")
      (node (ref "4") (pin "-") (pinfunction "-_-") (pintype "passive"))
      (node (ref "R7") (pin "2") (pinfunction "2_2") (pintype "passive"))
    )
    (net (code "18") (name "Net-(ANT1-D)") (class "Default")
      (node (ref "ANT1") (pin "1") (pinfunction "D_1") (pintype "bidirectional"))
      (node (ref "C10") (pin "2") (pinfunction "2_2") (pintype "passive"))
      (node (ref "C9") (pin "2") (pinfunction "2_2") (pintype "passive"))
    )
    (net (code "19") (name "Net-(C5-Pad1)") (class "Default")
      (node (ref "C5") (pin "1") (pinfunction "1_1") (pintype "passive"))
      (node (ref "L2") (pin "P$2") (pinfunction "P$2_P$2") (pintype "passive"))
    )
    (net (code "20") (name "Net-(C11-Pad2)") (class "Default")
      (node (ref "C11") (pin "2") (pinfunction "2_2") (pintype "passive"))
      (node (ref "C5") (pin "2") (pinfunction "2_2") (pintype "passive"))
      (node (ref "C9") (pin "1") (pinfunction "1_1") (pintype "passive"))
    )
    (net (code "21") (name "Net-(Q1-D)") (class "Default")
      (node (ref "Q1") (pin "3") (pinfunction "D_3") (pintype "passive"))
      (node (ref "R23") (pin "1") (pinfunction "1_1") (pintype "passive"))
      (node (ref "R24") (pin "2") (pinfunction "2_2") (pintype "passive"))
    )
    (net (code "22") (name "Net-(Q2-B)") (class "Default")
      (node (ref "Q2") (pin "1") (pinfunction "B_1") (pintype "passive"))
      (node (ref "R1") (pin "2") (pinfunction "2_2") (pintype "passive"))
    )
    (net (code "23") (name "Net-(Q3-B)") (class "Default")
      (node (ref "Q3") (pin "1") (pinfunction "B_1") (pintype "passive"))
      (node (ref "R3") (pin "2") (pinfunction "2_2") (pintype "passive"))
    )
    (net (code "24") (name "Net-(Q5-D)") (class "Default")
      (node (ref "C26") (pin "2") (pinfunction "2_2") (pintype "passive"))
      (node (ref "Q5") (pin "3") (pinfunction "D_3") (pintype "passive"))
      (node (ref "U9") (pin "F") (pinfunction "RH2_RED_F") (pintype "bidirectional"))
      (node (ref "U9") (pin "G") (pinfunction "RS2_RED_G") (pintype "bidirectional"))
      (node (ref "U9") (pin "H") (pinfunction "RH2_OX_H") (pintype "bidirectional"))
      (node (ref "U9") (pin "J") (pinfunction "RS2_OX_J") (pintype "bidirectional"))
    )
    (net (code "25") (name "Net-(R37-Pad2)") (class "Default")
      (node (ref "R37") (pin "2") (pinfunction "2_2") (pintype "passive"))
      (node (ref "U6") (pin "TXD") (pinfunction "TXD_TXD") (pintype "bidirectional"))
    )
    (net (code "26") (name "Net-(RELOAD-B1)") (class "Default")
      (node (ref "R13") (pin "1") (pinfunction "1_1") (pintype "passive"))
      (node (ref "RELOAD") (pin "3") (pinfunction "B1_3") (pintype "bidirectional"))
    )
    (net (code "27") (name "Net-(RESET-B1)") (class "Default")
      (node (ref "R4") (pin "1") (pinfunction "1_1") (pintype "passive"))
      (node (ref "RESET") (pin "3") (pinfunction "B1_3") (pintype "bidirectional"))
    )
    (net (code "28") (name "Net-(U2-TXD)") (class "Default")
      (node (ref "R34") (pin "2") (pinfunction "2_2") (pintype "passive"))
      (node (ref "U2") (pin "3") (pinfunction "TXD_3") (pintype "output"))
    )
    (net (code "29") (name "Net-(U2-UD+)") (class "Default")
      (node (ref "U2") (pin "6") (pinfunction "UD+_6") (pintype "bidirectional"))
      (node (ref "USB1") (pin "3") (pinfunction "D+_3") (pintype "bidirectional"))
    )
    (net (code "30") (name "Net-(U2-UD-)") (class "Default")
      (node (ref "U2") (pin "7") (pinfunction "UD-_7") (pintype "bidirectional"))
      (node (ref "USB1") (pin "2") (pinfunction "D-_2") (pintype "bidirectional"))
    )
    (net (code "31") (name "Net-(U2-XI)") (class "Default")
      (node (ref "C18") (pin "2") (pinfunction "2_2") (pintype "passive"))
      (node (ref "U2") (pin "9") (pinfunction "XI_9") (pintype "input"))
      (node (ref "Y1") (pin "2") (pinfunction "2_2") (pintype "passive"))
    )
    (net (code "32") (name "Net-(U2-XO)") (class "Default")
      (node (ref "C19") (pin "2") (pinfunction "2_2") (pintype "passive"))
      (node (ref "U2") (pin "10") (pinfunction "XO_10") (pintype "output"))
      (node (ref "Y1") (pin "1") (pinfunction "1_1") (pintype "passive"))
    )
    (net (code "33") (name "Net-(U4-RFIN)") (class "Default")
      (node (ref "L1") (pin "2") (pinfunction "2_2") (pintype "passive"))
      (node (ref "L2") (pin "P$1") (pinfunction "P$1_P$1") (pintype "passive"))
      (node (ref "U4") (pin "3") (pinfunction "RFIN_3") (pintype "bidirectional"))
    )
    (net (code "34") (name "Net-(U4-VCC)") (class "Default")
      (node (ref "C12") (pin "2") (pinfunction "2_2") (pintype "passive"))
      (node (ref "C15") (pin "2") (pinfunction "2_2") (pintype "passive"))
      (node (ref "R5") (pin "2") (pinfunction "2_2") (pintype "passive"))
      (node (ref "U4") (pin "4") (pinfunction "VCC_4") (pintype "power_in"))
    )
    (net (code "35") (name "Net-(U4-~{SHDN})") (class "Default")
      (node (ref "R6") (pin "2") (pinfunction "2_2") (pintype "passive"))
      (node (ref "U4") (pin "5") (pinfunction "~{SHDN}_5") (pintype "bidirectional"))
    )
    (net (code "36") (name "Net-(U5-RESERVED)") (class "Default")
      (node (ref "R18") (pin "2") (pinfunction "2_2") (pintype "passive"))
      (node (ref "U5") (pin "16") (pinfunction "RESERVED_16") (pintype "bidirectional"))
    )
    (net (code "37") (name "Net-(U5-RESERVED1)") (class "Default")
      (node (ref "R19") (pin "2") (pinfunction "2_2") (pintype "passive"))
      (node (ref "U5") (pin "17") (pinfunction "RESERVED1_17") (pintype "bidirectional"))
    )
    (net (code "38") (name "Net-(U5-TXD1)") (class "Default")
      (node (ref "R38") (pin "1") (pinfunction "1_1") (pintype "passive"))
      (node (ref "U5") (pin "2") (pinfunction "TXD1_2") (pintype "bidirectional"))
    )
    (net (code "39") (name "Net-(U5-V_BCKP)") (class "Default")
      (node (ref "BAT1") (pin "+1") (pinfunction "V+_+1") (pintype "bidirectional"))
      (node (ref "BAT1") (pin "+2") (pinfunction "V+_+2") (pintype "bidirectional"))
      (node (ref "U5") (pin "6") (pinfunction "V_BCKP_6") (pintype "bidirectional"))
    )
    (net (code "40") (name "Net-(U7-SD3)") (class "Default")
      (node (ref "R35") (pin "2") (pinfunction "2_2") (pintype "passive"))
      (node (ref "U7") (pin "18") (pinfunction "SD3_18") (pintype "bidirectional"))
    )
    (net (code "41") (name "Net-(U7-TXD0)") (class "Default")
      (node (ref "R33") (pin "2") (pinfunction "2_2") (pintype "passive"))
      (node (ref "U7") (pin "35") (pinfunction "TXD0_35") (pintype "output"))
    )
    (net (code "42") (name "Net-(U9-RH1_OX)") (class "Default")
      (node (ref "R23") (pin "2") (pinfunction "2_2") (pintype "passive"))
      (node (ref "U9") (pin "A") (pinfunction "RH1_OX_A") (pintype "bidirectional"))
    )
    (net (code "43") (name "Net-(U9-RH1_RED)") (class "Default")
      (node (ref "R21") (pin "2") (pinfunction "2_2") (pintype "passive"))
      (node (ref "U9") (pin "C") (pinfunction "RH1_RED_C") (pintype "bidirectional"))
    )
    (net (code "44") (name "Net-(USB1-VBUS)") (class "Default")
      (node (ref "L3") (pin "1") (pinfunction "1_1") (pintype "passive"))
      (node (ref "USB1") (pin "1") (pinfunction "VBUS_1") (pintype "power_in"))
    )
    (net (code "45") (name "PM_RESET") (class "Default")
      (node (ref "U6") (pin "RESET") (pinfunction "RESET_RESET") (pintype "bidirectional"))
      (node (ref "U7") (pin "28") (pinfunction "IO17_28") (pintype "bidirectional"))
    )
    (net (code "46") (name "PM_SET") (class "Default")
      (node (ref "U6") (pin "SET") (pinfunction "SET_SET") (pintype "bidirectional"))
      (node (ref "U7") (pin "29") (pinfunction "IO5_29") (pintype "bidirectional"))
    )
    (net (code "47") (name "RELOAD") (class "Default")
      (node (ref "C4") (pin "2") (pinfunction "2_2") (pintype "passive"))
      (node (ref "RELOAD") (pin "2") (pinfunction "B0_2") (pintype "bidirectional"))
      (node (ref "U7") (pin "4") (pinfunction "IO36/SEN_VP/A1_0_4") (pintype "passive"))
    )
    (net (code "48") (name "RESET") (class "Default")
      (node (ref "C3") (pin "2") (pinfunction "2_2") (pintype "passive"))
      (node (ref "Q3") (pin "2") (pinfunction "E_2") (pintype "passive"))
      (node (ref "RESET") (pin "2") (pinfunction "B0_2") (pintype "bidirectional"))
      (node (ref "U7") (pin "3") (pinfunction "EN_3") (pintype "input"))
    )
    (net (code "49") (name "RF_IN") (class "Default")
      (node (ref "U4") (pin "6") (pinfunction "RFOUT_6") (pintype "bidirectional"))
      (node (ref "U5") (pin "11") (pinfunction "RF_IN_11") (pintype "bidirectional"))
    )
    (net (code "50") (name "RTS") (class "Default")
      (node (ref "Q3") (pin "3") (pinfunction "C_3") (pintype "passive"))
      (node (ref "R1") (pin "1") (pinfunction "1_1") (pintype "passive"))
      (node (ref "U2") (pin "16") (pinfunction "RTS#_16") (pintype "output"))
    )
    (net (code "51") (name "RXD0") (class "Default")
      (node (ref "R34") (pin "1") (pinfunction "1_1") (pintype "passive"))
      (node (ref "U7") (pin "34") (pinfunction "RXD0_34") (pintype "input"))
    )
    (net (code "52") (name "SCL") (class "Default")
      (node (ref "R22") (pin "1") (pinfunction "1_1") (pintype "passive"))
      (node (ref "U1") (pin "6") (pinfunction "SCL_6") (pintype "input"))
      (node (ref "U7") (pin "12") (pinfunction "IO27/A2_7_12") (pintype "bidirectional"))
    )
    (net (code "53") (name "SDA") (class "Default")
      (node (ref "R10") (pin "1") (pinfunction "1_1") (pintype "passive"))
      (node (ref "U1") (pin "1") (pinfunction "SDA_1") (pintype "bidirectional"))
      (node (ref "U7") (pin "11") (pinfunction "IO26/DAC2/A2_9_11") (pintype "bidirectional"))
    )
    (net (code "54") (name "SD_CLK_IO14") (class "Default")
      (node (ref "R15") (pin "1") (pinfunction "1_1") (pintype "passive"))
      (node (ref "SD1") (pin "5") (pinfunction "SCLK_5") (pintype "bidirectional"))
      (node (ref "U7") (pin "13") (pinfunction "IO14/A2_6_13") (pintype "bidirectional"))
    )
    (net (code "55") (name "SD_CMD_IO15") (class "Default")
      (node (ref "R17") (pin "1") (pinfunction "1_1") (pintype "passive"))
      (node (ref "SD1") (pin "3") (pinfunction "DI_3") (pintype "bidirectional"))
      (node (ref "U7") (pin "23") (pinfunction "IO15/A2_3_23") (pintype "bidirectional"))
    )
    (net (code "56") (name "SD_CS_IO13") (class "Default")
      (node (ref "R8") (pin "1") (pinfunction "1_1") (pintype "passive"))
      (node (ref "SD1") (pin "2") (pinfunction "CS_2") (pintype "bidirectional"))
      (node (ref "U7") (pin "16") (pinfunction "IO13/A2_4_16") (pintype "bidirectional"))
    )
    (net (code "57") (name "SD_D0_IO2") (class "Default")
      (node (ref "R12") (pin "2") (pinfunction "2_2") (pintype "passive"))
      (node (ref "R9") (pin "1") (pinfunction "1_1") (pintype "passive"))
      (node (ref "SD1") (pin "7") (pinfunction "DO_7") (pintype "bidirectional"))
      (node (ref "U7") (pin "24") (pinfunction "IO2/A2_2_24") (pintype "bidirectional"))
    )
    (net (code "58") (name "SD_D1_IO4") (class "Default")
      (node (ref "SD1") (pin "8") (pinfunction "DATA1_8") (pintype "bidirectional"))
      (node (ref "U7") (pin "26") (pinfunction "IO4/A2_0_26") (pintype "bidirectional"))
    )
    (net (code "59") (name "SD_D2_IO12") (class "Default")
      (node (ref "SD1") (pin "1") (pinfunction "DATA2_1") (pintype "bidirectional"))
      (node (ref "U7") (pin "14") (pinfunction "IO12/A2_5_14") (pintype "bidirectional"))
    )
    (net (code "60") (name "STANDBY") (class "Default")
      (node (ref "U5") (pin "5") (pinfunction "STANDBY_5") (pintype "bidirectional"))
      (node (ref "U7") (pin "36") (pinfunction "IO22_36") (pintype "bidirectional"))
    )
    (net (code "61") (name "STAT_LED1") (class "Default")
      (node (ref "R14") (pin "2") (pinfunction "2_2") (pintype "passive"))
      (node (ref "U7") (pin "33") (pinfunction "IO21_33") (pintype "bidirectional"))
    )
    (net (code "62") (name "STAT_LED2") (class "Default")
      (node (ref "R16") (pin "2") (pinfunction "2_2") (pintype "passive"))
      (node (ref "U7") (pin "31") (pinfunction "IO19_31") (pintype "bidirectional"))
    )
    (net (code "63") (name "STAT_LED3") (class "Default")
      (node (ref "R2") (pin "2") (pinfunction "2_2") (pintype "passive"))
      (node (ref "U7") (pin "30") (pinfunction "IO18_30") (pintype "bidirectional"))
    )
    (net (code "64") (name "TIMER") (class "Default")
      (node (ref "U5") (pin "18") (pinfunction "TIMER_18") (pintype "bidirectional"))
      (node (ref "U7") (pin "37") (pinfunction "IO23_37") (pintype "bidirectional"))
    )
    (net (code "65") (name "TXD0") (class "Default")
      (node (ref "R33") (pin "1") (pinfunction "1_1") (pintype "passive"))
      (node (ref "U2") (pin "4") (pinfunction "RXD_4") (pintype "input"))
    )
    (net (code "66") (name "U1RXD") (class "Default")
      (node (ref "R38") (pin "2") (pinfunction "2_2") (pintype "passive"))
      (node (ref "U7") (pin "17") (pinfunction "SD2_17") (pintype "bidirectional"))
    )
    (net (code "67") (name "U1TXD") (class "Default")
      (node (ref "R35") (pin "1") (pinfunction "1_1") (pintype "passive"))
      (node (ref "U5") (pin "3") (pinfunction "RXD1_3") (pintype "bidirectional"))
    )
    (net (code "68") (name "U2RXD") (class "Default")
      (node (ref "R37") (pin "1") (pinfunction "1_1") (pintype "passive"))
      (node (ref "U7") (pin "27") (pinfunction "IO16_27") (pintype "bidirectional"))
    )
    (net (code "69") (name "VCC_RF") (class "Default")
      (node (ref "R5") (pin "1") (pinfunction "1_1") (pintype "passive"))
      (node (ref "U5") (pin "14") (pinfunction "VCC_RF_14") (pintype "power_in"))
    )
    (net (code "70") (name "VOX_RAWA") (class "Default")
      (node (ref "R20") (pin "2") (pinfunction "2_2") (pintype "passive"))
      (node (ref "U8") (pin "3") (pinfunction "3_3") (pintype "bidirectional"))
      (node (ref "U9") (pin "B") (pinfunction "RS1_OX_B") (pintype "bidirectional"))
    )
    (net (code "71") (name "VOX_RAWB") (class "Default")
      (node (ref "U7") (pin "9") (pinfunction "IO33/A1_5/X32N_9") (pintype "bidirectional"))
      (node (ref "U8") (pin "1") (pinfunction "1_1") (pintype "bidirectional"))
      (node (ref "U8") (pin "2") (pinfunction "2_2") (pintype "bidirectional"))
    )
    (net (code "72") (name "VRED_RAWA") (class "Default")
      (node (ref "R11") (pin "2") (pinfunction "2_2") (pintype "passive"))
      (node (ref "U8") (pin "5") (pinfunction "5_5") (pintype "bidirectional"))
      (node (ref "U9") (pin "D") (pinfunction "RS1_RED_D") (pintype "bidirectional"))
    )
    (net (code "73") (name "VRED_RAWB") (class "Default")
      (node (ref "U7") (pin "10") (pinfunction "IO25/DAC1/A2_8_10") (pintype "bidirectional"))
      (node (ref "U8") (pin "6") (pinfunction "6_6") (pintype "bidirectional"))
      (node (ref "U8") (pin "7") (pinfunction "7_7") (pintype "bidirectional"))
    )
    (net (code "74") (name "unconnected-(SD1-CDN-Pad9)") (class "Default")
      (node (ref "SD1") (pin "9") (pinfunction "CDN_9") (pintype "bidirectional"))
    )
    (net (code "75") (name "unconnected-(U2-ACT#-Pad2)") (class "Default")
      (node (ref "U2") (pin "2") (pinfunction "ACT#_2") (pintype "output"))
    )
    (net (code "76") (name "unconnected-(U2-CKO-Pad1)") (class "Default")
      (node (ref "U2") (pin "1") (pinfunction "CKO_1") (pintype "output"))
    )
    (net (code "77") (name "unconnected-(U2-CTS#-Pad11)") (class "Default")
      (node (ref "U2") (pin "11") (pinfunction "CTS#_11") (pintype "input"))
    )
    (net (code "78") (name "unconnected-(U2-DCD#-Pad14)") (class "Default")
      (node (ref "U2") (pin "14") (pinfunction "DCD#_14") (pintype "input"))
    )
    (net (code "79") (name "unconnected-(U2-DSR#-Pad12)") (class "Default")
      (node (ref "U2") (pin "12") (pinfunction "DSR#_12") (pintype "input"))
    )
    (net (code "80") (name "unconnected-(U2-NC-Pad17)") (class "Default")
      (node (ref "U2") (pin "17") (pinfunction "NC_17") (pintype "no_connect"))
    )
    (net (code "81") (name "unconnected-(U2-R232-Pad18)") (class "Default")
      (node (ref "U2") (pin "18") (pinfunction "R232_18") (pintype "input"))
    )
    (net (code "82") (name "unconnected-(U2-RI#-Pad13)") (class "Default")
      (node (ref "U2") (pin "13") (pinfunction "RI#_13") (pintype "input"))
    )
    (net (code "83") (name "unconnected-(U5-NC-Pad7)") (class "Default")
      (node (ref "U5") (pin "7") (pinfunction "NC_7") (pintype "bidirectional"))
    )
    (net (code "84") (name "unconnected-(U5-NC-Pad15)") (class "Default")
      (node (ref "U5") (pin "15") (pinfunction "NC_15") (pintype "bidirectional"))
    )
    (net (code "85") (name "unconnected-(U6-PadRXD)") (class "Default")
      (node (ref "U6") (pin "RXD") (pinfunction "RXD_RXD") (pintype "bidirectional"))
    )
    (net (code "86") (name "unconnected-(U7-IO39{slash}SEN_VN{slash}A1_3-Pad5)") (class "Default")
      (node (ref "U7") (pin "5") (pinfunction "IO39/SEN_VN/A1_3_5") (pintype "passive"))
    )
    (net (code "87") (name "unconnected-(USB1-ID-Pad4)") (class "Default")
      (node (ref "USB1") (pin "4") (pinfunction "ID_4") (pintype "bidirectional"))
    )
  )
)
